# F405Pill.net
KiCad netlist of a schematic drawn in EAGLE
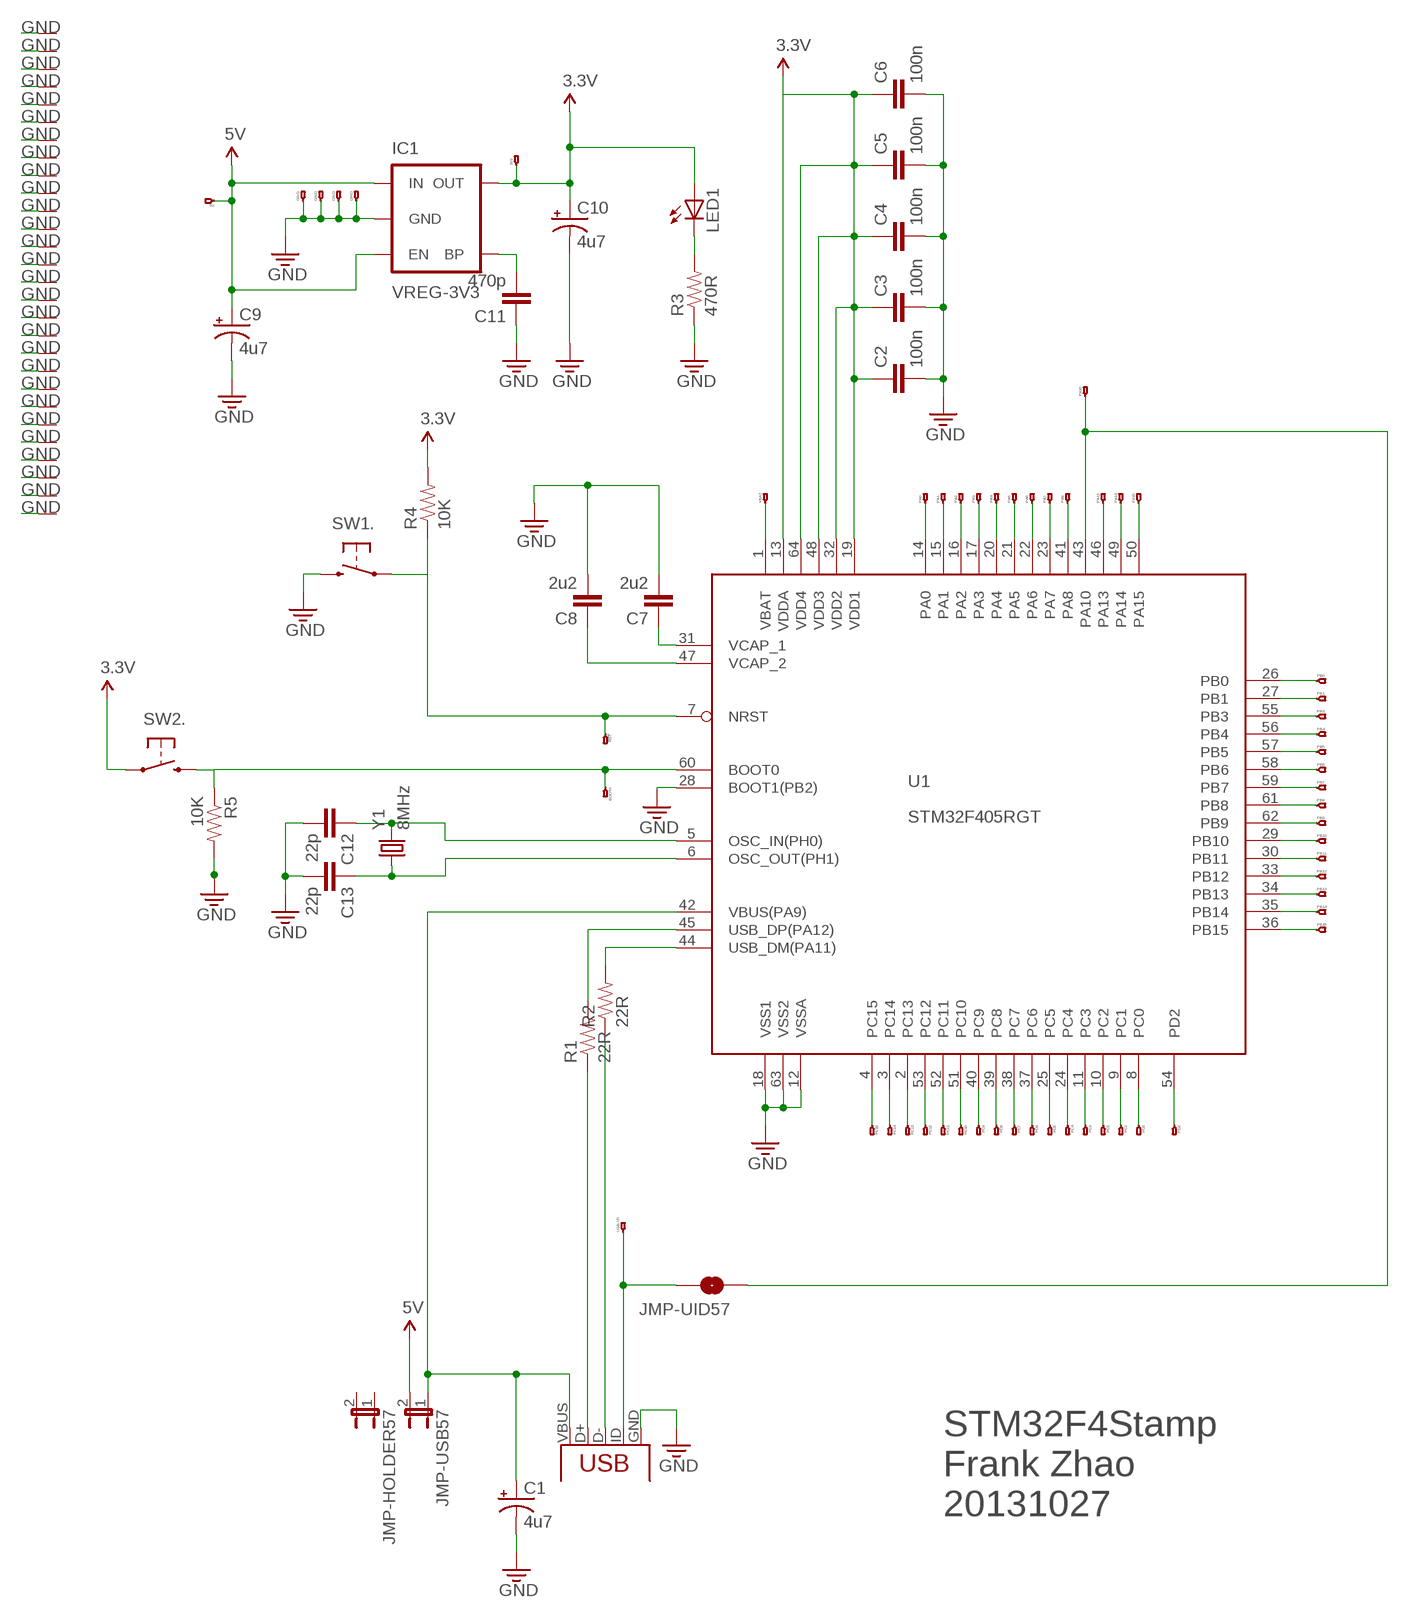
[diagram p0: schematic, sheet 1]

(export (version "E")
  (design (tool "Eeschema 10.0.6"))
  (components
    (comp (ref "C1")
      (value "4u7")
      (footprint "eagle-import:EIA3216-KIT")
      (libsource (lib "eagle-import") (part "CAP_POL1206-KIT"))
    )
    (comp (ref "C2")
      (value "100n")
      (footprint "eagle-import:0603-CAP")
      (libsource (lib "eagle-import") (part "CAP0603-CAP"))
    )
    (comp (ref "C3")
      (value "100n")
      (footprint "eagle-import:0603-CAP")
      (libsource (lib "eagle-import") (part "CAP0603-CAP"))
    )
    (comp (ref "C4")
      (value "100n")
      (footprint "eagle-import:0603-CAP")
      (libsource (lib "eagle-import") (part "CAP0603-CAP"))
    )
    (comp (ref "C5")
      (value "100n")
      (footprint "eagle-import:0603-CAP")
      (libsource (lib "eagle-import") (part "CAP0603-CAP"))
    )
    (comp (ref "C6")
      (value "100n")
      (footprint "eagle-import:0603-CAP")
      (libsource (lib "eagle-import") (part "CAP0603-CAP"))
    )
    (comp (ref "C7")
      (value "2u2")
      (footprint "eagle-import:0603-CAP")
      (libsource (lib "eagle-import") (part "CAP0603-CAP"))
    )
    (comp (ref "C8")
      (value "2u2")
      (footprint "eagle-import:0603-CAP")
      (libsource (lib "eagle-import") (part "CAP0603-CAP"))
    )
    (comp (ref "C9")
      (value "4u7")
      (footprint "eagle-import:EIA3216-KIT")
      (libsource (lib "eagle-import") (part "CAP_POL1206-KIT"))
    )
    (comp (ref "C10")
      (value "4u7")
      (footprint "eagle-import:EIA3216-KIT")
      (libsource (lib "eagle-import") (part "CAP_POL1206-KIT"))
    )
    (comp (ref "C11")
      (value "470p")
      (footprint "eagle-import:0603-CAP")
      (libsource (lib "eagle-import") (part "CAP0603-CAP"))
    )
    (comp (ref "C12")
      (value "22p")
      (footprint "eagle-import:0603-CAP")
      (libsource (lib "eagle-import") (part "CAP0603-CAP"))
    )
    (comp (ref "C13")
      (value "22p")
      (footprint "eagle-import:0603-CAP")
      (libsource (lib "eagle-import") (part "CAP0603-CAP"))
    )
    (comp (ref "IC1")
      (value "VREG-3V3")
      (footprint "eagle-import:SOT23-5")
      (libsource (lib "eagle-import") (part "V_REG_LDOSMD"))
    )
    (comp (ref "JMP-HOLDER57")
      (value "JUMPER-2-PTH-2MM")
      (footprint "eagle-import:1X02_2MM_TH")
      (libsource (lib "eagle-import") (part "JUMPER-2-PTH-2MM"))
    )
    (comp (ref "JMP-UID57")
      (value "SOLDERJUMPERNC")
      (footprint "eagle-import:SJ_2S")
      (libsource (lib "eagle-import") (part "SOLDERJUMPERNC"))
    )
    (comp (ref "JMP-USB57")
      (value "JUMPER-2-PTH-2MM")
      (footprint "eagle-import:1X02_2MM_TH")
      (libsource (lib "eagle-import") (part "JUMPER-2-PTH-2MM"))
    )
    (comp (ref "JP2")
      (value "5V")
      (footprint "eagle-import:1X1-HEADER-HOLE")
      (libsource (lib "eagle-import") (part "HEADERHOLE-HEADERHOLE"))
    )
    (comp (ref "JP3")
      (value "GND")
      (footprint "eagle-import:1X1-HEADER-HOLE")
      (libsource (lib "eagle-import") (part "HEADERHOLE-HEADERHOLE"))
    )
    (comp (ref "JP4")
      (value "3V3")
      (footprint "eagle-import:1X1-HEADER-HOLE")
      (libsource (lib "eagle-import") (part "HEADERHOLE-HEADERHOLE"))
    )
    (comp (ref "JP5")
      (value "GND")
      (footprint "eagle-import:1X1-HEADER-HOLE")
      (libsource (lib "eagle-import") (part "HEADERHOLE-HEADERHOLE"))
    )
    (comp (ref "JP6")
      (value "GND")
      (footprint "eagle-import:1X1-HEADER-HOLE")
      (libsource (lib "eagle-import") (part "HEADERHOLE-HEADERHOLE"))
    )
    (comp (ref "JP7")
      (value "GND")
      (footprint "eagle-import:1X1-HEADER-HOLE")
      (libsource (lib "eagle-import") (part "HEADERHOLE-HEADERHOLE"))
    )
    (comp (ref "JP8")
      (value "PB8")
      (footprint "eagle-import:1X1-HEADER-HOLE")
      (libsource (lib "eagle-import") (part "HEADERHOLE-HEADERHOLE"))
    )
    (comp (ref "JP9")
      (value "PA10")
      (footprint "eagle-import:1X1-HEADER-HOLE")
      (libsource (lib "eagle-import") (part "HEADERHOLE-HEADERHOLE"))
    )
    (comp (ref "JP10")
      (value "PA8")
      (footprint "eagle-import:1X1-HEADER-HOLE")
      (libsource (lib "eagle-import") (part "HEADERHOLE-HEADERHOLE"))
    )
    (comp (ref "JP11")
      (value "PA13")
      (footprint "eagle-import:1X1-HEADER-HOLE")
      (libsource (lib "eagle-import") (part "HEADERHOLE-HEADERHOLE"))
    )
    (comp (ref "JP12")
      (value "PC9")
      (footprint "eagle-import:1X1-HEADER-HOLE")
      (libsource (lib "eagle-import") (part "HEADERHOLE-HEADERHOLE"))
    )
    (comp (ref "JP13")
      (value "PC15")
      (footprint "eagle-import:1X1-HEADER-HOLE")
      (libsource (lib "eagle-import") (part "HEADERHOLE-HEADERHOLE"))
    )
    (comp (ref "JP14")
      (value "PC14")
      (footprint "eagle-import:1X1-HEADER-HOLE")
      (libsource (lib "eagle-import") (part "HEADERHOLE-HEADERHOLE"))
    )
    (comp (ref "JP15")
      (value "PC13")
      (footprint "eagle-import:1X1-HEADER-HOLE")
      (libsource (lib "eagle-import") (part "HEADERHOLE-HEADERHOLE"))
    )
    (comp (ref "JP16")
      (value "PC12")
      (footprint "eagle-import:1X1-HEADER-HOLE")
      (libsource (lib "eagle-import") (part "HEADERHOLE-HEADERHOLE"))
    )
    (comp (ref "JP17")
      (value "PC11")
      (footprint "eagle-import:1X1-HEADER-HOLE")
      (libsource (lib "eagle-import") (part "HEADERHOLE-HEADERHOLE"))
    )
    (comp (ref "JP18")
      (value "PC10")
      (footprint "eagle-import:1X1-HEADER-HOLE")
      (libsource (lib "eagle-import") (part "HEADERHOLE-HEADERHOLE"))
    )
    (comp (ref "JP19")
      (value "PC8")
      (footprint "eagle-import:1X1-HEADER-HOLE")
      (libsource (lib "eagle-import") (part "HEADERHOLE-HEADERHOLE"))
    )
    (comp (ref "JP20")
      (value "PC7")
      (footprint "eagle-import:1X1-HEADER-HOLE")
      (libsource (lib "eagle-import") (part "HEADERHOLE-HEADERHOLE"))
    )
    (comp (ref "JP21")
      (value "PC6")
      (footprint "eagle-import:1X1-HEADER-HOLE")
      (libsource (lib "eagle-import") (part "HEADERHOLE-HEADERHOLE"))
    )
    (comp (ref "JP22")
      (value "PC5")
      (footprint "eagle-import:1X1-HEADER-HOLE")
      (libsource (lib "eagle-import") (part "HEADERHOLE-HEADERHOLE"))
    )
    (comp (ref "JP23")
      (value "PC4")
      (footprint "eagle-import:1X1-HEADER-HOLE")
      (libsource (lib "eagle-import") (part "HEADERHOLE-HEADERHOLE"))
    )
    (comp (ref "JP24")
      (value "PC3")
      (footprint "eagle-import:1X1-HEADER-HOLE")
      (libsource (lib "eagle-import") (part "HEADERHOLE-HEADERHOLE"))
    )
    (comp (ref "JP25")
      (value "PC2")
      (footprint "eagle-import:1X1-HEADER-HOLE")
      (libsource (lib "eagle-import") (part "HEADERHOLE-HEADERHOLE"))
    )
    (comp (ref "JP26")
      (value "PC1")
      (footprint "eagle-import:1X1-HEADER-HOLE")
      (libsource (lib "eagle-import") (part "HEADERHOLE-HEADERHOLE"))
    )
    (comp (ref "JP27")
      (value "PC0")
      (footprint "eagle-import:1X1-HEADER-HOLE")
      (libsource (lib "eagle-import") (part "HEADERHOLE-HEADERHOLE"))
    )
    (comp (ref "JP28")
      (value "PD2")
      (footprint "eagle-import:1X1-HEADER-HOLE")
      (libsource (lib "eagle-import") (part "HEADERHOLE-HEADERHOLE"))
    )
    (comp (ref "JP29")
      (value "PA0")
      (footprint "eagle-import:1X1-HEADER-HOLE")
      (libsource (lib "eagle-import") (part "HEADERHOLE-HEADERHOLE"))
    )
    (comp (ref "JP30")
      (value "PA1")
      (footprint "eagle-import:1X1-HEADER-HOLE")
      (libsource (lib "eagle-import") (part "HEADERHOLE-HEADERHOLE"))
    )
    (comp (ref "JP31")
      (value "PA2")
      (footprint "eagle-import:1X1-HEADER-HOLE")
      (libsource (lib "eagle-import") (part "HEADERHOLE-HEADERHOLE"))
    )
    (comp (ref "JP32")
      (value "PA3")
      (footprint "eagle-import:1X1-HEADER-HOLE")
      (libsource (lib "eagle-import") (part "HEADERHOLE-HEADERHOLE"))
    )
    (comp (ref "JP33")
      (value "PA4")
      (footprint "eagle-import:1X1-HEADER-HOLE")
      (libsource (lib "eagle-import") (part "HEADERHOLE-HEADERHOLE"))
    )
    (comp (ref "JP34")
      (value "PA5")
      (footprint "eagle-import:1X1-HEADER-HOLE")
      (libsource (lib "eagle-import") (part "HEADERHOLE-HEADERHOLE"))
    )
    (comp (ref "JP35")
      (value "PA6")
      (footprint "eagle-import:1X1-HEADER-HOLE")
      (libsource (lib "eagle-import") (part "HEADERHOLE-HEADERHOLE"))
    )
    (comp (ref "JP36")
      (value "PA7")
      (footprint "eagle-import:1X1-HEADER-HOLE")
      (libsource (lib "eagle-import") (part "HEADERHOLE-HEADERHOLE"))
    )
    (comp (ref "JP37")
      (value "PA14")
      (footprint "eagle-import:1X1-HEADER-HOLE")
      (libsource (lib "eagle-import") (part "HEADERHOLE-HEADERHOLE"))
    )
    (comp (ref "JP38")
      (value "PA15")
      (footprint "eagle-import:1X1-HEADER-HOLE")
      (libsource (lib "eagle-import") (part "HEADERHOLE-HEADERHOLE"))
    )
    (comp (ref "JP39")
      (value "PB0")
      (footprint "eagle-import:1X1-HEADER-HOLE")
      (libsource (lib "eagle-import") (part "HEADERHOLE-HEADERHOLE"))
    )
    (comp (ref "JP40")
      (value "PB1")
      (footprint "eagle-import:1X1-HEADER-HOLE")
      (libsource (lib "eagle-import") (part "HEADERHOLE-HEADERHOLE"))
    )
    (comp (ref "JP41")
      (value "PB3")
      (footprint "eagle-import:1X1-HEADER-HOLE")
      (libsource (lib "eagle-import") (part "HEADERHOLE-HEADERHOLE"))
    )
    (comp (ref "JP42")
      (value "PB4")
      (footprint "eagle-import:1X1-HEADER-HOLE")
      (libsource (lib "eagle-import") (part "HEADERHOLE-HEADERHOLE"))
    )
    (comp (ref "JP43")
      (value "PB5")
      (footprint "eagle-import:1X1-HEADER-HOLE")
      (libsource (lib "eagle-import") (part "HEADERHOLE-HEADERHOLE"))
    )
    (comp (ref "JP44")
      (value "PB6")
      (footprint "eagle-import:1X1-HEADER-HOLE")
      (libsource (lib "eagle-import") (part "HEADERHOLE-HEADERHOLE"))
    )
    (comp (ref "JP45")
      (value "PB7")
      (footprint "eagle-import:1X1-HEADER-HOLE")
      (libsource (lib "eagle-import") (part "HEADERHOLE-HEADERHOLE"))
    )
    (comp (ref "JP46")
      (value "PB9")
      (footprint "eagle-import:1X1-HEADER-HOLE")
      (libsource (lib "eagle-import") (part "HEADERHOLE-HEADERHOLE"))
    )
    (comp (ref "JP47")
      (value "PB10")
      (footprint "eagle-import:1X1-HEADER-HOLE")
      (libsource (lib "eagle-import") (part "HEADERHOLE-HEADERHOLE"))
    )
    (comp (ref "JP48")
      (value "PB11")
      (footprint "eagle-import:1X1-HEADER-HOLE")
      (libsource (lib "eagle-import") (part "HEADERHOLE-HEADERHOLE"))
    )
    (comp (ref "JP49")
      (value "PB12")
      (footprint "eagle-import:1X1-HEADER-HOLE")
      (libsource (lib "eagle-import") (part "HEADERHOLE-HEADERHOLE"))
    )
    (comp (ref "JP50")
      (value "PB13")
      (footprint "eagle-import:1X1-HEADER-HOLE")
      (libsource (lib "eagle-import") (part "HEADERHOLE-HEADERHOLE"))
    )
    (comp (ref "JP51")
      (value "PB14")
      (footprint "eagle-import:1X1-HEADER-HOLE")
      (libsource (lib "eagle-import") (part "HEADERHOLE-HEADERHOLE"))
    )
    (comp (ref "JP52")
      (value "PB15")
      (footprint "eagle-import:1X1-HEADER-HOLE")
      (libsource (lib "eagle-import") (part "HEADERHOLE-HEADERHOLE"))
    )
    (comp (ref "JP53")
      (value "VBAT")
      (footprint "eagle-import:1X1-HEADER-HOLE")
      (libsource (lib "eagle-import") (part "HEADERHOLE-HEADERHOLE"))
    )
    (comp (ref "JP54")
      (value "!RST")
      (footprint "eagle-import:1X1-HEADER-HOLE")
      (libsource (lib "eagle-import") (part "HEADERHOLE-HEADERHOLE"))
    )
    (comp (ref "JP55")
      (value "BOOT0")
      (footprint "eagle-import:1X1-HEADER-HOLE")
      (libsource (lib "eagle-import") (part "HEADERHOLE-HEADERHOLE"))
    )
    (comp (ref "JP56")
      (value "USB-ID")
      (footprint "eagle-import:1X1-HEADER-HOLE")
      (libsource (lib "eagle-import") (part "HEADERHOLE-HEADERHOLE"))
    )
    (comp (ref "LED1")
      (value "LED0603")
      (footprint "eagle-import:LED-0603")
      (libsource (lib "eagle-import") (part "LED0603"))
    )
    (comp (ref "R1")
      (value "22R")
      (footprint "eagle-import:0603-RES")
      (libsource (lib "eagle-import") (part "RESISTOR0603-RES"))
    )
    (comp (ref "R2")
      (value "22R")
      (footprint "eagle-import:0603-RES")
      (libsource (lib "eagle-import") (part "RESISTOR0603-RES"))
    )
    (comp (ref "R3")
      (value "470R")
      (footprint "eagle-import:0603-RES")
      (libsource (lib "eagle-import") (part "RESISTOR0603-RES"))
    )
    (comp (ref "R4")
      (value "10K")
      (footprint "eagle-import:0603-RES")
      (libsource (lib "eagle-import") (part "RESISTOR0603-RES"))
    )
    (comp (ref "R5")
      (value "10K")
      (footprint "eagle-import:0603-RES")
      (libsource (lib "eagle-import") (part "RESISTOR0603-RES"))
    )
    (comp (ref "SW1")
      (value "!RST")
      (footprint "eagle-import:SWITCH-TACT-B3U-1100P-B")
      (libsource (lib "eagle-import") (part "SWITCH-B3U-1110-BOSS"))
    )
    (comp (ref "SW2")
      (value "BOOT")
      (footprint "eagle-import:SWITCH-TACT-B3U-1100P-B")
      (libsource (lib "eagle-import") (part "SWITCH-B3U-1110-BOSS"))
    )
    (comp (ref "U1")
      (value "STM32F405RGT")
      (footprint "eagle-import:LQFP64")
      (libsource (lib "eagle-import") (part "STM32F405RGT"))
    )
    (comp (ref "USB57")
      (value "USB-MICROB-SMD")
      (footprint "eagle-import:USB-MICROB-SMD")
      (libsource (lib "eagle-import") (part "USB-MICROB-SMD"))
    )
    (comp (ref "VP_0")
      (value "VPDEV0")
      (footprint "eagle-import:VPAC0")
      (libsource (lib "eagle-import") (part "VPDEV0"))
    )
    (comp (ref "VP_1")
      (value "VPDEV0")
      (footprint "eagle-import:VPAC0")
      (libsource (lib "eagle-import") (part "VPDEV0"))
    )
    (comp (ref "VP_2")
      (value "VPDEV0")
      (footprint "eagle-import:VPAC0")
      (libsource (lib "eagle-import") (part "VPDEV0"))
    )
    (comp (ref "VP_3")
      (value "VPDEV0")
      (footprint "eagle-import:VPAC0")
      (libsource (lib "eagle-import") (part "VPDEV0"))
    )
    (comp (ref "VP_4")
      (value "VPDEV0")
      (footprint "eagle-import:VPAC0")
      (libsource (lib "eagle-import") (part "VPDEV0"))
    )
    (comp (ref "VP_5")
      (value "VPDEV0")
      (footprint "eagle-import:VPAC0")
      (libsource (lib "eagle-import") (part "VPDEV0"))
    )
    (comp (ref "VP_6")
      (value "VPDEV0")
      (footprint "eagle-import:VPAC0")
      (libsource (lib "eagle-import") (part "VPDEV0"))
    )
    (comp (ref "VP_7")
      (value "VPDEV0")
      (footprint "eagle-import:VPAC0")
      (libsource (lib "eagle-import") (part "VPDEV0"))
    )
    (comp (ref "VP_8")
      (value "VPDEV0")
      (footprint "eagle-import:VPAC0")
      (libsource (lib "eagle-import") (part "VPDEV0"))
    )
    (comp (ref "VP_9")
      (value "VPDEV0")
      (footprint "eagle-import:VPAC0")
      (libsource (lib "eagle-import") (part "VPDEV0"))
    )
    (comp (ref "VP_10")
      (value "VPDEV0")
      (footprint "eagle-import:VPAC0")
      (libsource (lib "eagle-import") (part "VPDEV0"))
    )
    (comp (ref "VP_11")
      (value "VPDEV0")
      (footprint "eagle-import:VPAC0")
      (libsource (lib "eagle-import") (part "VPDEV0"))
    )
    (comp (ref "VP_12")
      (value "VPDEV0")
      (footprint "eagle-import:VPAC0")
      (libsource (lib "eagle-import") (part "VPDEV0"))
    )
    (comp (ref "VP_13")
      (value "VPDEV0")
      (footprint "eagle-import:VPAC0")
      (libsource (lib "eagle-import") (part "VPDEV0"))
    )
    (comp (ref "VP_14")
      (value "VPDEV0")
      (footprint "eagle-import:VPAC0")
      (libsource (lib "eagle-import") (part "VPDEV0"))
    )
    (comp (ref "VP_15")
      (value "VPDEV0")
      (footprint "eagle-import:VPAC0")
      (libsource (lib "eagle-import") (part "VPDEV0"))
    )
    (comp (ref "VP_16")
      (value "VPDEV0")
      (footprint "eagle-import:VPAC0")
      (libsource (lib "eagle-import") (part "VPDEV0"))
    )
    (comp (ref "VP_17")
      (value "VPDEV0")
      (footprint "eagle-import:VPAC0")
      (libsource (lib "eagle-import") (part "VPDEV0"))
    )
    (comp (ref "VP_18")
      (value "VPDEV0")
      (footprint "eagle-import:VPAC0")
      (libsource (lib "eagle-import") (part "VPDEV0"))
    )
    (comp (ref "VP_19")
      (value "VPDEV0")
      (footprint "eagle-import:VPAC0")
      (libsource (lib "eagle-import") (part "VPDEV0"))
    )
    (comp (ref "VP_20")
      (value "VPDEV0")
      (footprint "eagle-import:VPAC0")
      (libsource (lib "eagle-import") (part "VPDEV0"))
    )
    (comp (ref "VP_21")
      (value "VPDEV0")
      (footprint "eagle-import:VPAC0")
      (libsource (lib "eagle-import") (part "VPDEV0"))
    )
    (comp (ref "VP_22")
      (value "VPDEV0")
      (footprint "eagle-import:VPAC0")
      (libsource (lib "eagle-import") (part "VPDEV0"))
    )
    (comp (ref "VP_23")
      (value "VPDEV0")
      (footprint "eagle-import:VPAC0")
      (libsource (lib "eagle-import") (part "VPDEV0"))
    )
    (comp (ref "VP_24")
      (value "VPDEV0")
      (footprint "eagle-import:VPAC0")
      (libsource (lib "eagle-import") (part "VPDEV0"))
    )
    (comp (ref "VP_25")
      (value "VPDEV0")
      (footprint "eagle-import:VPAC0")
      (libsource (lib "eagle-import") (part "VPDEV0"))
    )
    (comp (ref "VP_26")
      (value "VPDEV0")
      (footprint "eagle-import:VPAC0")
      (libsource (lib "eagle-import") (part "VPDEV0"))
    )
    (comp (ref "VP_27")
      (value "VPDEV0")
      (footprint "eagle-import:VPAC0")
      (libsource (lib "eagle-import") (part "VPDEV0"))
    )
    (comp (ref "Y1")
      (value "8MHz")
      (footprint "eagle-import:CRYSTAL-SMD-5X3")
      (libsource (lib "eagle-import") (part "CRYSTAL5X3"))
    )
  )
  (nets
    (net (code "1") (name "3.3V") (class "Default")
      (node (ref "C10") (pin "A") (pinfunction "+_A") (pintype "passive"))
      (node (ref "C2") (pin "1") (pinfunction "1_1") (pintype "passive"))
      (node (ref "C3") (pin "1") (pinfunction "1_1") (pintype "passive"))
      (node (ref "C4") (pin "1") (pinfunction "1_1") (pintype "passive"))
      (node (ref "C5") (pin "1") (pinfunction "1_1") (pintype "passive"))
      (node (ref "C6") (pin "1") (pinfunction "1_1") (pintype "passive"))
      (node (ref "IC1") (pin "5") (pinfunction "OUT_5") (pintype "passive"))
      (node (ref "JP4") (pin "1") (pinfunction "P$1_1") (pintype "bidirectional"))
      (node (ref "LED1") (pin "A") (pinfunction "A_A") (pintype "passive"))
      (node (ref "R4") (pin "2") (pinfunction "2_2") (pintype "passive"))
      (node (ref "SW2") (pin "1") (pinfunction "1_1") (pintype "passive"))
      (node (ref "U1") (pin "13") (pinfunction "VDDA_13") (pintype "power_in"))
      (node (ref "U1") (pin "19") (pinfunction "VDD1_19") (pintype "power_in"))
      (node (ref "U1") (pin "32") (pinfunction "VDD2_32") (pintype "power_in"))
      (node (ref "U1") (pin "48") (pinfunction "VDD3_48") (pintype "power_in"))
      (node (ref "U1") (pin "64") (pinfunction "VDD4_64") (pintype "power_in"))
    )
    (net (code "2") (name "5V") (class "Default")
      (node (ref "C9") (pin "A") (pinfunction "+_A") (pintype "passive"))
      (node (ref "IC1") (pin "1") (pinfunction "IN_1") (pintype "input"))
      (node (ref "IC1") (pin "3") (pinfunction "EN_3") (pintype "input"))
      (node (ref "JMP-USB57") (pin "2") (pinfunction "2_2") (pintype "passive"))
      (node (ref "JP2") (pin "1") (pinfunction "P$1_1") (pintype "bidirectional"))
    )
    (net (code "3") (name "GND") (class "Default")
      (node (ref "C1") (pin "C") (pinfunction "-_C") (pintype "passive"))
      (node (ref "C10") (pin "C") (pinfunction "-_C") (pintype "passive"))
      (node (ref "C11") (pin "1") (pinfunction "1_1") (pintype "passive"))
      (node (ref "C12") (pin "2") (pinfunction "2_2") (pintype "passive"))
      (node (ref "C13") (pin "2") (pinfunction "2_2") (pintype "passive"))
      (node (ref "C2") (pin "2") (pinfunction "2_2") (pintype "passive"))
      (node (ref "C3") (pin "2") (pinfunction "2_2") (pintype "passive"))
      (node (ref "C4") (pin "2") (pinfunction "2_2") (pintype "passive"))
      (node (ref "C5") (pin "2") (pinfunction "2_2") (pintype "passive"))
      (node (ref "C6") (pin "2") (pinfunction "2_2") (pintype "passive"))
      (node (ref "C7") (pin "2") (pinfunction "2_2") (pintype "passive"))
      (node (ref "C8") (pin "2") (pinfunction "2_2") (pintype "passive"))
      (node (ref "C9") (pin "C") (pinfunction "-_C") (pintype "passive"))
      (node (ref "IC1") (pin "2") (pinfunction "GND_2") (pintype "input"))
      (node (ref "JP3") (pin "1") (pinfunction "P$1_1") (pintype "bidirectional"))
      (node (ref "JP5") (pin "1") (pinfunction "P$1_1") (pintype "bidirectional"))
      (node (ref "JP6") (pin "1") (pinfunction "P$1_1") (pintype "bidirectional"))
      (node (ref "JP7") (pin "1") (pinfunction "P$1_1") (pintype "bidirectional"))
      (node (ref "R3") (pin "1") (pinfunction "1_1") (pintype "passive"))
      (node (ref "R5") (pin "2") (pinfunction "2_2") (pintype "passive"))
      (node (ref "SW1") (pin "2") (pinfunction "2_2") (pintype "passive"))
      (node (ref "SW1") (pin "BOSS") (pinfunction "P$1_BOSS") (pintype "bidirectional"))
      (node (ref "SW2") (pin "BOSS") (pinfunction "P$1_BOSS") (pintype "bidirectional"))
      (node (ref "U1") (pin "12") (pinfunction "VSSA_12") (pintype "power_in"))
      (node (ref "U1") (pin "18") (pinfunction "VSS1_18") (pintype "power_in"))
      (node (ref "U1") (pin "28") (pinfunction "BOOT1(PB2)_28") (pintype "input"))
      (node (ref "U1") (pin "63") (pinfunction "VSS2_63") (pintype "power_in"))
      (node (ref "USB57") (pin "GND") (pinfunction "GND_GND") (pintype "bidirectional"))
      (node (ref "USB57") (pin "MT1") (pinfunction "P$1_MT1") (pintype "bidirectional"))
      (node (ref "USB57") (pin "MT2") (pinfunction "P$1_MT2") (pintype "bidirectional"))
      (node (ref "USB57") (pin "MT3") (pinfunction "P$1_MT3") (pintype "bidirectional"))
      (node (ref "USB57") (pin "MT4") (pinfunction "P$1_MT4") (pintype "bidirectional"))
      (node (ref "VP_0") (pin "VP") (pinfunction "VP_VP") (pintype "passive"))
      (node (ref "VP_1") (pin "VP") (pinfunction "VP_VP") (pintype "passive"))
      (node (ref "VP_10") (pin "VP") (pinfunction "VP_VP") (pintype "passive"))
      (node (ref "VP_11") (pin "VP") (pinfunction "VP_VP") (pintype "passive"))
      (node (ref "VP_12") (pin "VP") (pinfunction "VP_VP") (pintype "passive"))
      (node (ref "VP_13") (pin "VP") (pinfunction "VP_VP") (pintype "passive"))
      (node (ref "VP_14") (pin "VP") (pinfunction "VP_VP") (pintype "passive"))
      (node (ref "VP_15") (pin "VP") (pinfunction "VP_VP") (pintype "passive"))
      (node (ref "VP_16") (pin "VP") (pinfunction "VP_VP") (pintype "passive"))
      (node (ref "VP_17") (pin "VP") (pinfunction "VP_VP") (pintype "passive"))
      (node (ref "VP_18") (pin "VP") (pinfunction "VP_VP") (pintype "passive"))
      (node (ref "VP_19") (pin "VP") (pinfunction "VP_VP") (pintype "passive"))
      (node (ref "VP_2") (pin "VP") (pinfunction "VP_VP") (pintype "passive"))
      (node (ref "VP_20") (pin "VP") (pinfunction "VP_VP") (pintype "passive"))
      (node (ref "VP_21") (pin "VP") (pinfunction "VP_VP") (pintype "passive"))
      (node (ref "VP_22") (pin "VP") (pinfunction "VP_VP") (pintype "passive"))
      (node (ref "VP_23") (pin "VP") (pinfunction "VP_VP") (pintype "passive"))
      (node (ref "VP_24") (pin "VP") (pinfunction "VP_VP") (pintype "passive"))
      (node (ref "VP_25") (pin "VP") (pinfunction "VP_VP") (pintype "passive"))
      (node (ref "VP_26") (pin "VP") (pinfunction "VP_VP") (pintype "passive"))
      (node (ref "VP_27") (pin "VP") (pinfunction "VP_VP") (pintype "passive"))
      (node (ref "VP_3") (pin "VP") (pinfunction "VP_VP") (pintype "passive"))
      (node (ref "VP_4") (pin "VP") (pinfunction "VP_VP") (pintype "passive"))
      (node (ref "VP_5") (pin "VP") (pinfunction "VP_VP") (pintype "passive"))
      (node (ref "VP_6") (pin "VP") (pinfunction "VP_VP") (pintype "passive"))
      (node (ref "VP_7") (pin "VP") (pinfunction "VP_VP") (pintype "passive"))
      (node (ref "VP_8") (pin "VP") (pinfunction "VP_VP") (pintype "passive"))
      (node (ref "VP_9") (pin "VP") (pinfunction "VP_VP") (pintype "passive"))
    )
    (net (code "4") (name "Net-(C1-+)") (class "Default")
      (node (ref "C1") (pin "A") (pinfunction "+_A") (pintype "passive"))
      (node (ref "JMP-USB57") (pin "1") (pinfunction "1_1") (pintype "passive"))
      (node (ref "U1") (pin "42") (pinfunction "VBUS(PA9)_42") (pintype "bidirectional"))
      (node (ref "USB57") (pin "VBUS") (pinfunction "VBUS_VBUS") (pintype "bidirectional"))
    )
    (net (code "5") (name "Net-(IC1-BP)") (class "Default")
      (node (ref "C11") (pin "2") (pinfunction "2_2") (pintype "passive"))
      (node (ref "IC1") (pin "4") (pinfunction "BP_4") (pintype "input"))
    )
    (net (code "6") (name "Net-(JP8-P$1)") (class "Default")
      (node (ref "JP8") (pin "1") (pinfunction "P$1_1") (pintype "bidirectional"))
      (node (ref "U1") (pin "61") (pinfunction "PB8_61") (pintype "bidirectional"))
    )
    (net (code "7") (name "Net-(JP9-P$1)") (class "Default")
      (node (ref "JMP-UID57") (pin "1") (pinfunction "1_1") (pintype "passive"))
      (node (ref "JP9") (pin "1") (pinfunction "P$1_1") (pintype "bidirectional"))
      (node (ref "U1") (pin "43") (pinfunction "PA10_43") (pintype "bidirectional"))
    )
    (net (code "8") (name "Net-(JP10-P$1)") (class "Default")
      (node (ref "JP10") (pin "1") (pinfunction "P$1_1") (pintype "bidirectional"))
      (node (ref "U1") (pin "41") (pinfunction "PA8_41") (pintype "bidirectional"))
    )
    (net (code "9") (name "Net-(JP11-P$1)") (class "Default")
      (node (ref "JP11") (pin "1") (pinfunction "P$1_1") (pintype "bidirectional"))
      (node (ref "U1") (pin "46") (pinfunction "PA13_46") (pintype "bidirectional"))
    )
    (net (code "10") (name "Net-(JP12-P$1)") (class "Default")
      (node (ref "JP12") (pin "1") (pinfunction "P$1_1") (pintype "bidirectional"))
      (node (ref "U1") (pin "40") (pinfunction "PC9_40") (pintype "bidirectional"))
    )
    (net (code "11") (name "Net-(JP13-P$1)") (class "Default")
      (node (ref "JP13") (pin "1") (pinfunction "P$1_1") (pintype "bidirectional"))
      (node (ref "U1") (pin "4") (pinfunction "PC15_4") (pintype "bidirectional"))
    )
    (net (code "12") (name "Net-(JP14-P$1)") (class "Default")
      (node (ref "JP14") (pin "1") (pinfunction "P$1_1") (pintype "bidirectional"))
      (node (ref "U1") (pin "3") (pinfunction "PC14_3") (pintype "bidirectional"))
    )
    (net (code "13") (name "Net-(JP15-P$1)") (class "Default")
      (node (ref "JP15") (pin "1") (pinfunction "P$1_1") (pintype "bidirectional"))
      (node (ref "U1") (pin "2") (pinfunction "PC13_2") (pintype "bidirectional"))
    )
    (net (code "14") (name "Net-(JP16-P$1)") (class "Default")
      (node (ref "JP16") (pin "1") (pinfunction "P$1_1") (pintype "bidirectional"))
      (node (ref "U1") (pin "53") (pinfunction "PC12_53") (pintype "bidirectional"))
    )
    (net (code "15") (name "Net-(JP17-P$1)") (class "Default")
      (node (ref "JP17") (pin "1") (pinfunction "P$1_1") (pintype "bidirectional"))
      (node (ref "U1") (pin "52") (pinfunction "PC11_52") (pintype "bidirectional"))
    )
    (net (code "16") (name "Net-(JP18-P$1)") (class "Default")
      (node (ref "JP18") (pin "1") (pinfunction "P$1_1") (pintype "bidirectional"))
      (node (ref "U1") (pin "51") (pinfunction "PC10_51") (pintype "bidirectional"))
    )
    (net (code "17") (name "Net-(JP19-P$1)") (class "Default")
      (node (ref "JP19") (pin "1") (pinfunction "P$1_1") (pintype "bidirectional"))
      (node (ref "U1") (pin "39") (pinfunction "PC8_39") (pintype "bidirectional"))
    )
    (net (code "18") (name "Net-(JP20-P$1)") (class "Default")
      (node (ref "JP20") (pin "1") (pinfunction "P$1_1") (pintype "bidirectional"))
      (node (ref "U1") (pin "38") (pinfunction "PC7_38") (pintype "bidirectional"))
    )
    (net (code "19") (name "Net-(JP21-P$1)") (class "Default")
      (node (ref "JP21") (pin "1") (pinfunction "P$1_1") (pintype "bidirectional"))
      (node (ref "U1") (pin "37") (pinfunction "PC6_37") (pintype "bidirectional"))
    )
    (net (code "20") (name "Net-(JP22-P$1)") (class "Default")
      (node (ref "JP22") (pin "1") (pinfunction "P$1_1") (pintype "bidirectional"))
      (node (ref "U1") (pin "25") (pinfunction "PC5_25") (pintype "bidirectional"))
    )
    (net (code "21") (name "Net-(JP23-P$1)") (class "Default")
      (node (ref "JP23") (pin "1") (pinfunction "P$1_1") (pintype "bidirectional"))
      (node (ref "U1") (pin "24") (pinfunction "PC4_24") (pintype "bidirectional"))
    )
    (net (code "22") (name "Net-(JP24-P$1)") (class "Default")
      (node (ref "JP24") (pin "1") (pinfunction "P$1_1") (pintype "bidirectional"))
      (node (ref "U1") (pin "11") (pinfunction "PC3_11") (pintype "bidirectional"))
    )
    (net (code "23") (name "Net-(JP25-P$1)") (class "Default")
      (node (ref "JP25") (pin "1") (pinfunction "P$1_1") (pintype "bidirectional"))
      (node (ref "U1") (pin "10") (pinfunction "PC2_10") (pintype "bidirectional"))
    )
    (net (code "24") (name "Net-(JP26-P$1)") (class "Default")
      (node (ref "JP26") (pin "1") (pinfunction "P$1_1") (pintype "bidirectional"))
      (node (ref "U1") (pin "9") (pinfunction "PC1_9") (pintype "bidirectional"))
    )
    (net (code "25") (name "Net-(JP27-P$1)") (class "Default")
      (node (ref "JP27") (pin "1") (pinfunction "P$1_1") (pintype "bidirectional"))
      (node (ref "U1") (pin "8") (pinfunction "PC0_8") (pintype "bidirectional"))
    )
    (net (code "26") (name "Net-(JP28-P$1)") (class "Default")
      (node (ref "JP28") (pin "1") (pinfunction "P$1_1") (pintype "bidirectional"))
      (node (ref "U1") (pin "54") (pinfunction "PD2_54") (pintype "bidirectional"))
    )
    (net (code "27") (name "Net-(JP29-P$1)") (class "Default")
      (node (ref "JP29") (pin "1") (pinfunction "P$1_1") (pintype "bidirectional"))
      (node (ref "U1") (pin "14") (pinfunction "PA0_14") (pintype "bidirectional"))
    )
    (net (code "28") (name "Net-(JP30-P$1)") (class "Default")
      (node (ref "JP30") (pin "1") (pinfunction "P$1_1") (pintype "bidirectional"))
      (node (ref "U1") (pin "15") (pinfunction "PA1_15") (pintype "bidirectional"))
    )
    (net (code "29") (name "Net-(JP31-P$1)") (class "Default")
      (node (ref "JP31") (pin "1") (pinfunction "P$1_1") (pintype "bidirectional"))
      (node (ref "U1") (pin "16") (pinfunction "PA2_16") (pintype "bidirectional"))
    )
    (net (code "30") (name "Net-(JP32-P$1)") (class "Default")
      (node (ref "JP32") (pin "1") (pinfunction "P$1_1") (pintype "bidirectional"))
      (node (ref "U1") (pin "17") (pinfunction "PA3_17") (pintype "bidirectional"))
    )
    (net (code "31") (name "Net-(JP33-P$1)") (class "Default")
      (node (ref "JP33") (pin "1") (pinfunction "P$1_1") (pintype "bidirectional"))
      (node (ref "U1") (pin "20") (pinfunction "PA4_20") (pintype "bidirectional"))
    )
    (net (code "32") (name "Net-(JP34-P$1)") (class "Default")
      (node (ref "JP34") (pin "1") (pinfunction "P$1_1") (pintype "bidirectional"))
      (node (ref "U1") (pin "21") (pinfunction "PA5_21") (pintype "bidirectional"))
    )
    (net (code "33") (name "Net-(JP35-P$1)") (class "Default")
      (node (ref "JP35") (pin "1") (pinfunction "P$1_1") (pintype "bidirectional"))
      (node (ref "U1") (pin "22") (pinfunction "PA6_22") (pintype "bidirectional"))
    )
    (net (code "34") (name "Net-(JP36-P$1)") (class "Default")
      (node (ref "JP36") (pin "1") (pinfunction "P$1_1") (pintype "bidirectional"))
      (node (ref "U1") (pin "23") (pinfunction "PA7_23") (pintype "bidirectional"))
    )
    (net (code "35") (name "Net-(JP37-P$1)") (class "Default")
      (node (ref "JP37") (pin "1") (pinfunction "P$1_1") (pintype "bidirectional"))
      (node (ref "U1") (pin "49") (pinfunction "PA14_49") (pintype "bidirectional"))
    )
    (net (code "36") (name "Net-(JP38-P$1)") (class "Default")
      (node (ref "JP38") (pin "1") (pinfunction "P$1_1") (pintype "bidirectional"))
      (node (ref "U1") (pin "50") (pinfunction "PA15_50") (pintype "bidirectional"))
    )
    (net (code "37") (name "Net-(JP39-P$1)") (class "Default")
      (node (ref "JP39") (pin "1") (pinfunction "P$1_1") (pintype "bidirectional"))
      (node (ref "U1") (pin "26") (pinfunction "PB0_26") (pintype "bidirectional"))
    )
    (net (code "38") (name "Net-(JP40-P$1)") (class "Default")
      (node (ref "JP40") (pin "1") (pinfunction "P$1_1") (pintype "bidirectional"))
      (node (ref "U1") (pin "27") (pinfunction "PB1_27") (pintype "bidirectional"))
    )
    (net (code "39") (name "Net-(JP41-P$1)") (class "Default")
      (node (ref "JP41") (pin "1") (pinfunction "P$1_1") (pintype "bidirectional"))
      (node (ref "U1") (pin "55") (pinfunction "PB3_55") (pintype "bidirectional"))
    )
    (net (code "40") (name "Net-(JP42-P$1)") (class "Default")
      (node (ref "JP42") (pin "1") (pinfunction "P$1_1") (pintype "bidirectional"))
      (node (ref "U1") (pin "56") (pinfunction "PB4_56") (pintype "bidirectional"))
    )
    (net (code "41") (name "Net-(JP43-P$1)") (class "Default")
      (node (ref "JP43") (pin "1") (pinfunction "P$1_1") (pintype "bidirectional"))
      (node (ref "U1") (pin "57") (pinfunction "PB5_57") (pintype "bidirectional"))
    )
    (net (code "42") (name "Net-(JP44-P$1)") (class "Default")
      (node (ref "JP44") (pin "1") (pinfunction "P$1_1") (pintype "bidirectional"))
      (node (ref "U1") (pin "58") (pinfunction "PB6_58") (pintype "bidirectional"))
    )
    (net (code "43") (name "Net-(JP45-P$1)") (class "Default")
      (node (ref "JP45") (pin "1") (pinfunction "P$1_1") (pintype "bidirectional"))
      (node (ref "U1") (pin "59") (pinfunction "PB7_59") (pintype "bidirectional"))
    )
    (net (code "44") (name "Net-(JP46-P$1)") (class "Default")
      (node (ref "JP46") (pin "1") (pinfunction "P$1_1") (pintype "bidirectional"))
      (node (ref "U1") (pin "62") (pinfunction "PB9_62") (pintype "bidirectional"))
    )
    (net (code "45") (name "Net-(JP47-P$1)") (class "Default")
      (node (ref "JP47") (pin "1") (pinfunction "P$1_1") (pintype "bidirectional"))
      (node (ref "U1") (pin "29") (pinfunction "PB10_29") (pintype "bidirectional"))
    )
    (net (code "46") (name "Net-(JP48-P$1)") (class "Default")
      (node (ref "JP48") (pin "1") (pinfunction "P$1_1") (pintype "bidirectional"))
      (node (ref "U1") (pin "30") (pinfunction "PB11_30") (pintype "bidirectional"))
    )
    (net (code "47") (name "Net-(JP49-P$1)") (class "Default")
      (node (ref "JP49") (pin "1") (pinfunction "P$1_1") (pintype "bidirectional"))
      (node (ref "U1") (pin "33") (pinfunction "PB12_33") (pintype "bidirectional"))
    )
    (net (code "48") (name "Net-(JP50-P$1)") (class "Default")
      (node (ref "JP50") (pin "1") (pinfunction "P$1_1") (pintype "bidirectional"))
      (node (ref "U1") (pin "34") (pinfunction "PB13_34") (pintype "bidirectional"))
    )
    (net (code "49") (name "Net-(JP51-P$1)") (class "Default")
      (node (ref "JP51") (pin "1") (pinfunction "P$1_1") (pintype "bidirectional"))
      (node (ref "U1") (pin "35") (pinfunction "PB14_35") (pintype "bidirectional"))
    )
    (net (code "50") (name "Net-(JP52-P$1)") (class "Default")
      (node (ref "JP52") (pin "1") (pinfunction "P$1_1") (pintype "bidirectional"))
      (node (ref "U1") (pin "36") (pinfunction "PB15_36") (pintype "bidirectional"))
    )
    (net (code "51") (name "Net-(JP53-P$1)") (class "Default")
      (node (ref "JP53") (pin "1") (pinfunction "P$1_1") (pintype "bidirectional"))
      (node (ref "U1") (pin "1") (pinfunction "VBAT_1") (pintype "power_in"))
    )
    (net (code "52") (name "Net-(JP54-P$1)") (class "Default")
      (node (ref "JP54") (pin "1") (pinfunction "P$1_1") (pintype "bidirectional"))
      (node (ref "R4") (pin "1") (pinfunction "1_1") (pintype "passive"))
      (node (ref "SW1") (pin "1") (pinfunction "1_1") (pintype "passive"))
      (node (ref "U1") (pin "7") (pinfunction "NRST_7") (pintype "input"))
    )
    (net (code "53") (name "Net-(JP55-P$1)") (class "Default")
      (node (ref "JP55") (pin "1") (pinfunction "P$1_1") (pintype "bidirectional"))
      (node (ref "R5") (pin "1") (pinfunction "1_1") (pintype "passive"))
      (node (ref "SW2") (pin "2") (pinfunction "2_2") (pintype "passive"))
      (node (ref "U1") (pin "60") (pinfunction "BOOT0_60") (pintype "input"))
    )
    (net (code "54") (name "Net-(JP56-P$1)") (class "Default")
      (node (ref "JMP-UID57") (pin "2") (pinfunction "2_2") (pintype "passive"))
      (node (ref "JP56") (pin "1") (pinfunction "P$1_1") (pintype "bidirectional"))
      (node (ref "USB57") (pin "ID") (pinfunction "ID_ID") (pintype "bidirectional"))
    )
    (net (code "55") (name "Net-(LED1-PadC)") (class "Default")
      (node (ref "LED1") (pin "C") (pinfunction "C_C") (pintype "passive"))
      (node (ref "R3") (pin "2") (pinfunction "2_2") (pintype "passive"))
    )
    (net (code "56") (name "Net-(R1-Pad1)") (class "Default")
      (node (ref "R1") (pin "1") (pinfunction "1_1") (pintype "passive"))
      (node (ref "USB57") (pin "D+") (pinfunction "D+_D+") (pintype "bidirectional"))
    )
    (net (code "57") (name "Net-(R2-Pad1)") (class "Default")
      (node (ref "R2") (pin "1") (pinfunction "1_1") (pintype "passive"))
      (node (ref "USB57") (pin "D-") (pinfunction "D-_D-") (pintype "bidirectional"))
    )
    (net (code "58") (name "Net-(U1-OSC_IN(PH0))") (class "Default")
      (node (ref "C12") (pin "1") (pinfunction "1_1") (pintype "passive"))
      (node (ref "U1") (pin "5") (pinfunction "OSC_IN(PH0)_5") (pintype "bidirectional"))
      (node (ref "Y1") (pin "3") (pinfunction "2_3") (pintype "passive"))
    )
    (net (code "59") (name "Net-(U1-OSC_OUT(PH1))") (class "Default")
      (node (ref "C13") (pin "1") (pinfunction "1_1") (pintype "passive"))
      (node (ref "U1") (pin "6") (pinfunction "OSC_OUT(PH1)_6") (pintype "bidirectional"))
      (node (ref "Y1") (pin "1") (pinfunction "1_1") (pintype "passive"))
    )
    (net (code "60") (name "Net-(U1-USB_DM(PA11))") (class "Default")
      (node (ref "R2") (pin "2") (pinfunction "2_2") (pintype "passive"))
      (node (ref "U1") (pin "44") (pinfunction "USB_DM(PA11)_44") (pintype "bidirectional"))
    )
    (net (code "61") (name "Net-(U1-USB_DP(PA12))") (class "Default")
      (node (ref "R1") (pin "2") (pinfunction "2_2") (pintype "passive"))
      (node (ref "U1") (pin "45") (pinfunction "USB_DP(PA12)_45") (pintype "bidirectional"))
    )
    (net (code "62") (name "Net-(U1-VCAP_1)") (class "Default")
      (node (ref "C7") (pin "1") (pinfunction "1_1") (pintype "passive"))
      (node (ref "U1") (pin "31") (pinfunction "VCAP_1_31") (pintype "bidirectional"))
    )
    (net (code "63") (name "Net-(U1-VCAP_2)") (class "Default")
      (node (ref "C8") (pin "1") (pinfunction "1_1") (pintype "passive"))
      (node (ref "U1") (pin "47") (pinfunction "VCAP_2_47") (pintype "bidirectional"))
    )
    (net (code "64") (name "unconnected-(JMP-HOLDER57-Pad1)") (class "Default")
      (node (ref "JMP-HOLDER57") (pin "1") (pinfunction "1_1") (pintype "passive"))
    )
    (net (code "65") (name "unconnected-(JMP-HOLDER57-Pad2)") (class "Default")
      (node (ref "JMP-HOLDER57") (pin "2") (pinfunction "2_2") (pintype "passive"))
    )
  )
)
